# stlink.net
KiCad netlist of a schematic drawn in Altium Designer
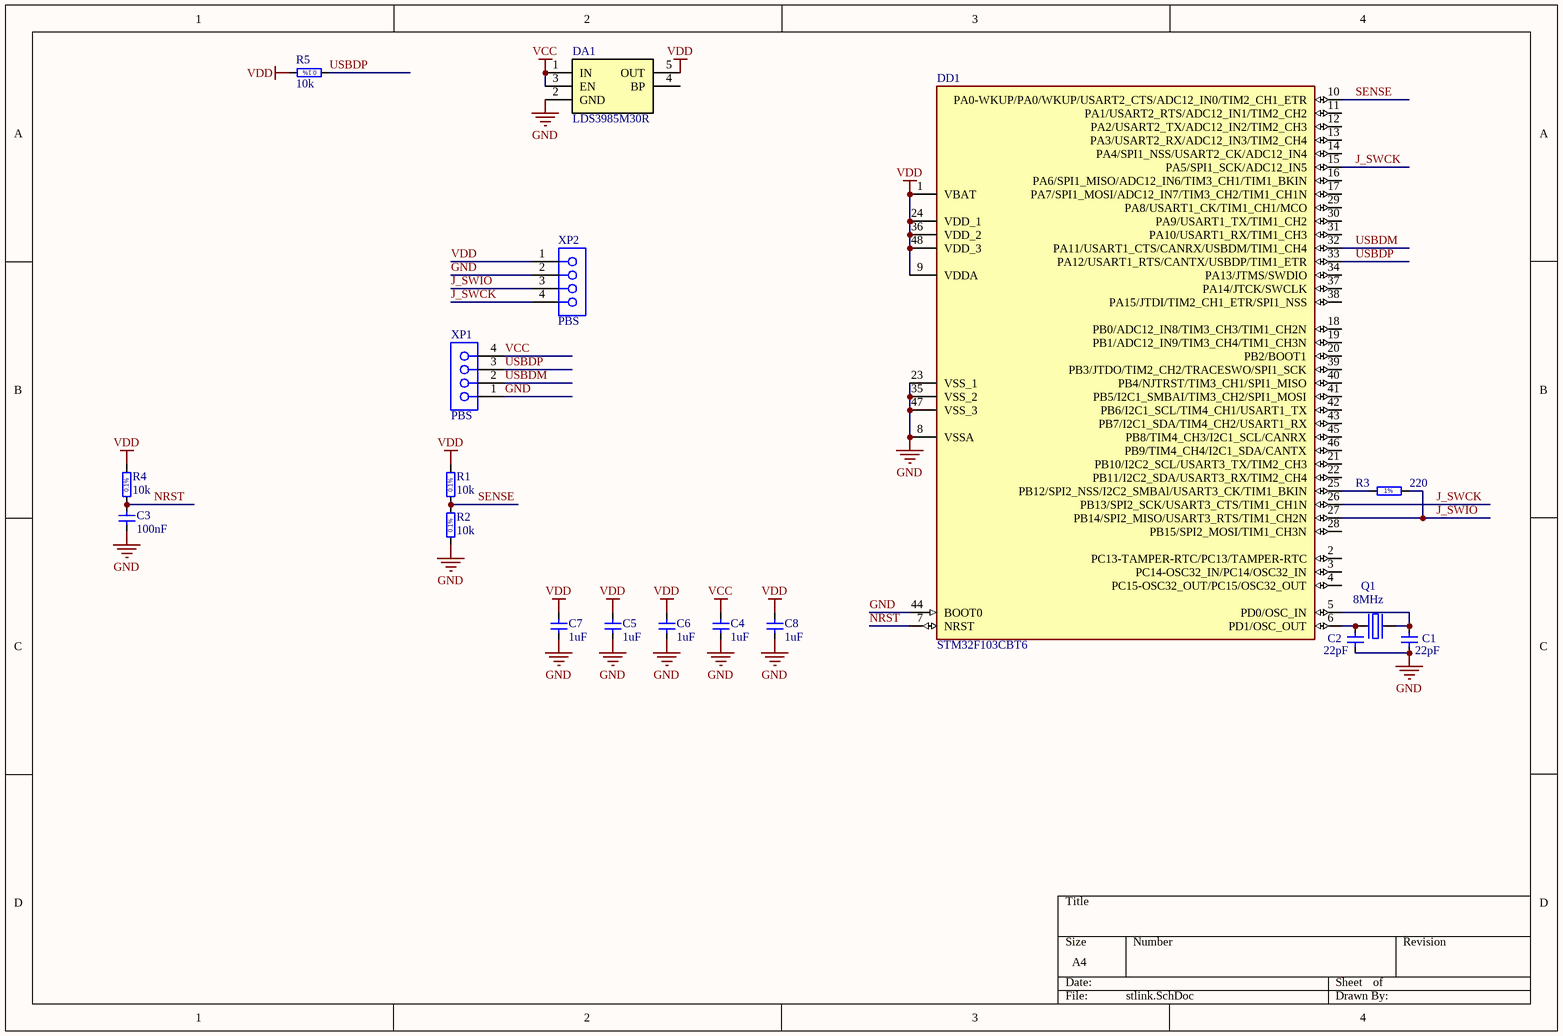
[diagram p0: stlink.SchDoc]

(export (version "E")
  (design (tool "Eeschema 10.0.6"))
  (components
    (comp (ref "C1")
      (value "22pF")
      (footprint "CAP0603R")
      (description "SMD 0805 Capacitor")
      (fields
        (field (name "PART NUMBER") "CC0603_22PF_50V_5%_NP0")
        (field (name "VOLTAGE") "50V")
        (field (name "AUTHOR") "I. Kuznetsov")
      )
      (libsource (lib "Capacitor") (part "CAP_NON_POLAR"))
    )
    (comp (ref "C2")
      (value "22pF")
      (footprint "CAP0603R")
      (description "SMD 0805 Capacitor")
      (fields
        (field (name "PART NUMBER") "CC0603_22PF_50V_5%_NP0")
        (field (name "VOLTAGE") "50V")
        (field (name "AUTHOR") "I. Kuznetsov")
      )
      (libsource (lib "Capacitor") (part "CAP_NON_POLAR"))
    )
    (comp (ref "C3")
      (value "100nF")
      (footprint "CAP0603R")
      (description "SMD 0805 Capacitor")
      (fields
        (field (name "PART NUMBER") "CC0603_100NF_100V_10%_X7R")
        (field (name "VOLTAGE") "100V")
        (field (name "AUTHOR") "I. Kuznetsov")
      )
      (libsource (lib "Capacitor") (part "CAP_NON_POLAR"))
    )
    (comp (ref "C4")
      (value "1uF")
      (footprint "CAP0603R")
      (description "SMD 0805 Capacitor")
      (fields
        (field (name "PART NUMBER") "CC0603_1UF_25V_10%_X7R")
        (field (name "VOLTAGE") "25V")
        (field (name "AUTHOR") "I. Kuznetsov")
      )
      (libsource (lib "Capacitor") (part "CAP_NON_POLAR"))
    )
    (comp (ref "C5")
      (value "1uF")
      (footprint "CAP0603R")
      (description "SMD 0805 Capacitor")
      (fields
        (field (name "PART NUMBER") "CC0603_1UF_25V_10%_X7R")
        (field (name "VOLTAGE") "25V")
        (field (name "AUTHOR") "I. Kuznetsov")
      )
      (libsource (lib "Capacitor") (part "CAP_NON_POLAR"))
    )
    (comp (ref "C6")
      (value "1uF")
      (footprint "CAP0603R")
      (description "SMD 0805 Capacitor")
      (fields
        (field (name "PART NUMBER") "CC0603_1UF_25V_10%_X7R")
        (field (name "VOLTAGE") "25V")
        (field (name "AUTHOR") "I. Kuznetsov")
      )
      (libsource (lib "Capacitor") (part "CAP_NON_POLAR"))
    )
    (comp (ref "C7")
      (value "1uF")
      (footprint "CAP0603R")
      (description "SMD 0805 Capacitor")
      (fields
        (field (name "PART NUMBER") "CC0603_1UF_25V_10%_X7R")
        (field (name "VOLTAGE") "25V")
        (field (name "AUTHOR") "I. Kuznetsov")
      )
      (libsource (lib "Capacitor") (part "CAP_NON_POLAR"))
    )
    (comp (ref "C8")
      (value "1uF")
      (footprint "CAP0603R")
      (description "SMD 0805 Capacitor")
      (fields
        (field (name "PART NUMBER") "CC0603_1UF_25V_10%_X7R")
        (field (name "VOLTAGE") "25V")
        (field (name "AUTHOR") "I. Kuznetsov")
      )
      (libsource (lib "Capacitor") (part "CAP_NON_POLAR"))
    )
    (comp (ref "DA1")
      (value "LDS3985M30R")
      (footprint "SOT23-5")
      (fields (field (name "MANUFACTURER") "ST") (field (name "AUTHOR") "I. Kuznetsov"))
      (libsource (lib "IC And Semiconductor") (part "REG_5_PIN"))
    )
    (comp (ref "DD1")
      (value "STM32F103CBT6")
      (footprint "LQFP48")
      (libsource (lib "IC And Semiconductor") (part "STM32F103X8_B-SQ48"))
    )
    (comp (ref "Q1")
      (value "8MHz")
      (footprint "XTAL_HC-49/U")
      (description "Quartz Crystal")
      (fields
        (field (name "PART NUMBER") "XTAL_20MHZ_AEL_HC-49/U")
        (field (name "MANUFACTURER") "AEL CRYSTALS")
        (field (name "AUTHOR") "CERN DEM JMW")
      )
      (libsource (lib "ICs And Semiconductors") (part "Quartz Crystal"))
    )
    (comp (ref "R1")
      (value "10k")
      (footprint "RES0603R")
      (fields
        (field (name "PART NUMBER") "R0603_10K_0.1%_0.063W_10PPM")
        (field (name "POWER") "0.063W")
        (field (name "TOLERANCE") "±0.1%")
        (field (name "AUTHOR") "CERN DEM JLC")
      )
      (libsource (lib "Resistor") (part "Resistor - 0.1%"))
    )
    (comp (ref "R2")
      (value "10k")
      (footprint "RES0603R")
      (fields
        (field (name "PART NUMBER") "R0603_10K_0.1%_0.063W_10PPM")
        (field (name "POWER") "0.063W")
        (field (name "TOLERANCE") "±0.1%")
        (field (name "AUTHOR") "CERN DEM JLC")
      )
      (libsource (lib "Resistor") (part "Resistor - 0.1%"))
    )
    (comp (ref "R3")
      (value "220")
      (footprint "RES0603R")
      (fields
        (field (name "PART NUMBER") "R0603_220R_1%_0.1W_100PPM")
        (field (name "POWER") "0.1W")
        (field (name "TOLERANCE") "±1%")
        (field (name "AUTHOR") "CERN DEM JLC")
      )
      (libsource (lib "Resistor") (part "Resistor - 1%"))
    )
    (comp (ref "R4")
      (value "10k")
      (footprint "RES0603R")
      (fields
        (field (name "PART NUMBER") "R0603_10K_0.1%_0.063W_10PPM")
        (field (name "POWER") "0.063W")
        (field (name "TOLERANCE") "±0.1%")
        (field (name "AUTHOR") "CERN DEM JLC")
      )
      (libsource (lib "Resistor") (part "Resistor - 0.1%"))
    )
    (comp (ref "R5")
      (value "10k")
      (footprint "RES0603R")
      (fields
        (field (name "PART NUMBER") "R0603_10K_0.1%_0.063W_10PPM")
        (field (name "POWER") "0.063W")
        (field (name "TOLERANCE") "±0.1%")
        (field (name "AUTHOR") "CERN DEM JLC")
      )
      (libsource (lib "Resistor") (part "Resistor - 0.1%"))
    )
    (comp (ref "XP1")
      (value "PBS")
      (footprint "PBS-04")
      (fields (field (name "PART NUMBER") "PBS-04"))
      (libsource (lib "") (part "CN_04S_1W_1"))
    )
    (comp (ref "XP2")
      (value "PBS")
      (footprint "PBS-04")
      (fields (field (name "PART NUMBER") "PBS-04"))
      (libsource (lib "Connector") (part "CN_04S_1W"))
    )
  )
  (nets
    (net (code "1") (name "/J_SWCK") (class "Default")
      (node (ref "DD1") (pin "15") (pinfunction "PA5/SPI1_SCK/ADC12_IN5_15") (pintype "bidirectional"))
      (node (ref "DD1") (pin "26") (pinfunction "PB13/SPI2_SCK/USART3_CTS/TIM1_CH1N_26") (pintype "bidirectional"))
      (node (ref "XP2") (pin "4") (pinfunction "4_4") (pintype "passive"))
    )
    (net (code "2") (name "/J_SWIO") (class "Default")
      (node (ref "DD1") (pin "27") (pinfunction "PB14/SPI2_MISO/USART3_RTS/TIM1_CH2N_27") (pintype "bidirectional"))
      (node (ref "R3") (pin "2") (pinfunction "2_2") (pintype "passive"))
      (node (ref "XP2") (pin "3") (pinfunction "3_3") (pintype "passive"))
    )
    (net (code "3") (name "/NRST") (class "Default")
      (node (ref "C3") (pin "2") (pinfunction "2_2") (pintype "passive"))
      (node (ref "DD1") (pin "7") (pinfunction "NRST_7") (pintype "bidirectional"))
      (node (ref "R4") (pin "1") (pinfunction "1_1") (pintype "passive"))
    )
    (net (code "4") (name "/SENSE") (class "Default")
      (node (ref "DD1") (pin "10") (pinfunction "PA0-WKUP/PA0/WKUP/USART2_CTS/ADC12_IN0/TIM2_CH1_ETR_10") (pintype "bidirectional"))
      (node (ref "R1") (pin "1") (pinfunction "1_1") (pintype "passive"))
      (node (ref "R2") (pin "2") (pinfunction "2_2") (pintype "passive"))
    )
    (net (code "5") (name "/USBDM") (class "Default")
      (node (ref "DD1") (pin "32") (pinfunction "PA11/USART1_CTS/CANRX/USBDM/TIM1_CH4_32") (pintype "bidirectional"))
      (node (ref "XP1") (pin "2") (pinfunction "2_2") (pintype "passive"))
    )
    (net (code "6") (name "/USBDP") (class "Default")
      (node (ref "DD1") (pin "33") (pinfunction "PA12/USART1_RTS/CANTX/USBDP/TIM1_ETR_33") (pintype "bidirectional"))
      (node (ref "R5") (pin "1") (pinfunction "1_1") (pintype "passive"))
      (node (ref "XP1") (pin "3") (pinfunction "3_3") (pintype "passive"))
    )
    (net (code "7") (name "GND") (class "Default")
      (node (ref "C1") (pin "1") (pinfunction "1_1") (pintype "passive"))
      (node (ref "C2") (pin "1") (pinfunction "1_1") (pintype "passive"))
      (node (ref "C3") (pin "1") (pinfunction "1_1") (pintype "passive"))
      (node (ref "C4") (pin "1") (pinfunction "1_1") (pintype "passive"))
      (node (ref "C5") (pin "1") (pinfunction "1_1") (pintype "passive"))
      (node (ref "C6") (pin "1") (pinfunction "1_1") (pintype "passive"))
      (node (ref "C7") (pin "1") (pinfunction "1_1") (pintype "passive"))
      (node (ref "C8") (pin "1") (pinfunction "1_1") (pintype "passive"))
      (node (ref "DA1") (pin "2") (pinfunction "GND_2") (pintype "passive"))
      (node (ref "DD1") (pin "23") (pinfunction "VSS_1_23") (pintype "power_in"))
      (node (ref "DD1") (pin "35") (pinfunction "VSS_2_35") (pintype "power_in"))
      (node (ref "DD1") (pin "44") (pinfunction "BOOT0_44") (pintype "input"))
      (node (ref "DD1") (pin "47") (pinfunction "VSS_3_47") (pintype "power_in"))
      (node (ref "DD1") (pin "8") (pinfunction "VSSA_8") (pintype "power_in"))
      (node (ref "R2") (pin "1") (pinfunction "1_1") (pintype "passive"))
      (node (ref "XP1") (pin "1") (pinfunction "1_1") (pintype "passive"))
      (node (ref "XP2") (pin "2") (pinfunction "2_2") (pintype "passive"))
    )
    (net (code "8") (name "Net-(DD1-PB12{slash}SPI2_NSS{slash}I2C2_SMBAl{slash}USART3_CK{slash}TIM1_BKIN)") (class "Default")
      (node (ref "DD1") (pin "25") (pinfunction "PB12/SPI2_NSS/I2C2_SMBAl/USART3_CK/TIM1_BKIN_25") (pintype "bidirectional"))
      (node (ref "R3") (pin "1") (pinfunction "1_1") (pintype "passive"))
    )
    (net (code "9") (name "Net-(DD1-PD0{slash}OSC_IN)") (class "Default")
      (node (ref "C1") (pin "2") (pinfunction "2_2") (pintype "passive"))
      (node (ref "DD1") (pin "5") (pinfunction "PD0/OSC_IN_5") (pintype "bidirectional"))
      (node (ref "Q1") (pin "2") (pinfunction "OSC2_2") (pintype "passive"))
    )
    (net (code "10") (name "Net-(DD1-PD1{slash}OSC_OUT)") (class "Default")
      (node (ref "C2") (pin "2") (pinfunction "2_2") (pintype "passive"))
      (node (ref "DD1") (pin "6") (pinfunction "PD1/OSC_OUT_6") (pintype "bidirectional"))
      (node (ref "Q1") (pin "1") (pinfunction "OSC1_1") (pintype "passive"))
    )
    (net (code "11") (name "VCC") (class "Default")
      (node (ref "C4") (pin "2") (pinfunction "2_2") (pintype "passive"))
      (node (ref "DA1") (pin "1") (pinfunction "IN_1") (pintype "passive"))
      (node (ref "DA1") (pin "3") (pinfunction "EN_3") (pintype "passive"))
      (node (ref "XP1") (pin "4") (pinfunction "4_4") (pintype "passive"))
    )
    (net (code "12") (name "VDD") (class "Default")
      (node (ref "C5") (pin "2") (pinfunction "2_2") (pintype "passive"))
      (node (ref "C6") (pin "2") (pinfunction "2_2") (pintype "passive"))
      (node (ref "C7") (pin "2") (pinfunction "2_2") (pintype "passive"))
      (node (ref "C8") (pin "2") (pinfunction "2_2") (pintype "passive"))
      (node (ref "DA1") (pin "5") (pinfunction "OUT_5") (pintype "passive"))
      (node (ref "DD1") (pin "1") (pinfunction "VBAT_1") (pintype "power_in"))
      (node (ref "DD1") (pin "24") (pinfunction "VDD_1_24") (pintype "power_in"))
      (node (ref "DD1") (pin "36") (pinfunction "VDD_2_36") (pintype "power_in"))
      (node (ref "DD1") (pin "48") (pinfunction "VDD_3_48") (pintype "power_in"))
      (node (ref "DD1") (pin "9") (pinfunction "VDDA_9") (pintype "power_in"))
      (node (ref "R1") (pin "2") (pinfunction "2_2") (pintype "passive"))
      (node (ref "R4") (pin "2") (pinfunction "2_2") (pintype "passive"))
      (node (ref "R5") (pin "2") (pinfunction "2_2") (pintype "passive"))
      (node (ref "XP2") (pin "1") (pinfunction "1_1") (pintype "passive"))
    )
    (net (code "13") (name "unconnected-(DA1-BP-Pad4)") (class "Default")
      (node (ref "DA1") (pin "4") (pinfunction "BP_4") (pintype "passive"))
    )
    (net (code "14") (name "unconnected-(DD1-PA1{slash}USART2_RTS{slash}ADC12_IN1{slash}TIM2_CH2-Pad11)") (class "Default")
      (node (ref "DD1") (pin "11") (pinfunction "PA1/USART2_RTS/ADC12_IN1/TIM2_CH2_11") (pintype "bidirectional"))
    )
    (net (code "15") (name "unconnected-(DD1-PA2{slash}USART2_TX{slash}ADC12_IN2{slash}TIM2_CH3-Pad12)") (class "Default")
      (node (ref "DD1") (pin "12") (pinfunction "PA2/USART2_TX/ADC12_IN2/TIM2_CH3_12") (pintype "bidirectional"))
    )
    (net (code "16") (name "unconnected-(DD1-PA3{slash}USART2_RX{slash}ADC12_IN3{slash}TIM2_CH4-Pad13)") (class "Default")
      (node (ref "DD1") (pin "13") (pinfunction "PA3/USART2_RX/ADC12_IN3/TIM2_CH4_13") (pintype "bidirectional"))
    )
    (net (code "17") (name "unconnected-(DD1-PA4{slash}SPI1_NSS{slash}USART2_CK{slash}ADC12_IN4-Pad14)") (class "Default")
      (node (ref "DD1") (pin "14") (pinfunction "PA4/SPI1_NSS/USART2_CK/ADC12_IN4_14") (pintype "bidirectional"))
    )
    (net (code "18") (name "unconnected-(DD1-PA6{slash}SPI1_MISO{slash}ADC12_IN6{slash}TIM3_CH1{slash}TIM1_BKIN-Pad16)") (class "Default")
      (node (ref "DD1") (pin "16") (pinfunction "PA6/SPI1_MISO/ADC12_IN6/TIM3_CH1/TIM1_BKIN_16") (pintype "bidirectional"))
    )
    (net (code "19") (name "unconnected-(DD1-PA7{slash}SPI1_MOSI{slash}ADC12_IN7{slash}TIM3_CH2{slash}TIM1_CH1N-Pad17)") (class "Default")
      (node (ref "DD1") (pin "17") (pinfunction "PA7/SPI1_MOSI/ADC12_IN7/TIM3_CH2/TIM1_CH1N_17") (pintype "bidirectional"))
    )
    (net (code "20") (name "unconnected-(DD1-PA8{slash}USART1_CK{slash}TIM1_CH1{slash}MCO-Pad29)") (class "Default")
      (node (ref "DD1") (pin "29") (pinfunction "PA8/USART1_CK/TIM1_CH1/MCO_29") (pintype "bidirectional"))
    )
    (net (code "21") (name "unconnected-(DD1-PA9{slash}USART1_TX{slash}TIM1_CH2-Pad30)") (class "Default")
      (node (ref "DD1") (pin "30") (pinfunction "PA9/USART1_TX/TIM1_CH2_30") (pintype "bidirectional"))
    )
    (net (code "22") (name "unconnected-(DD1-PA10{slash}USART1_RX{slash}TIM1_CH3-Pad31)") (class "Default")
      (node (ref "DD1") (pin "31") (pinfunction "PA10/USART1_RX/TIM1_CH3_31") (pintype "bidirectional"))
    )
    (net (code "23") (name "unconnected-(DD1-PA13{slash}JTMS{slash}SWDIO-Pad34)") (class "Default")
      (node (ref "DD1") (pin "34") (pinfunction "PA13/JTMS/SWDIO_34") (pintype "bidirectional"))
    )
    (net (code "24") (name "unconnected-(DD1-PA14{slash}JTCK{slash}SWCLK-Pad37)") (class "Default")
      (node (ref "DD1") (pin "37") (pinfunction "PA14/JTCK/SWCLK_37") (pintype "bidirectional"))
    )
    (net (code "25") (name "unconnected-(DD1-PA15{slash}JTDI{slash}TIM2_CH1_ETR{slash}SPI1_NSS-Pad38)") (class "Default")
      (node (ref "DD1") (pin "38") (pinfunction "PA15/JTDI/TIM2_CH1_ETR/SPI1_NSS_38") (pintype "bidirectional"))
    )
    (net (code "26") (name "unconnected-(DD1-PB0{slash}ADC12_IN8{slash}TIM3_CH3{slash}TIM1_CH2N-Pad18)") (class "Default")
      (node (ref "DD1") (pin "18") (pinfunction "PB0/ADC12_IN8/TIM3_CH3/TIM1_CH2N_18") (pintype "bidirectional"))
    )
    (net (code "27") (name "unconnected-(DD1-PB1{slash}ADC12_IN9{slash}TIM3_CH4{slash}TIM1_CH3N-Pad19)") (class "Default")
      (node (ref "DD1") (pin "19") (pinfunction "PB1/ADC12_IN9/TIM3_CH4/TIM1_CH3N_19") (pintype "bidirectional"))
    )
    (net (code "28") (name "unconnected-(DD1-PB2{slash}BOOT1-Pad20)") (class "Default")
      (node (ref "DD1") (pin "20") (pinfunction "PB2/BOOT1_20") (pintype "bidirectional"))
    )
    (net (code "29") (name "unconnected-(DD1-PB3{slash}JTDO{slash}TIM2_CH2{slash}TRACESWO{slash}SPI1_SCK-Pad39)") (class "Default")
      (node (ref "DD1") (pin "39") (pinfunction "PB3/JTDO/TIM2_CH2/TRACESWO/SPI1_SCK_39") (pintype "bidirectional"))
    )
    (net (code "30") (name "unconnected-(DD1-PB4{slash}NJTRST{slash}TIM3_CH1{slash}SPI1_MISO-Pad40)") (class "Default")
      (node (ref "DD1") (pin "40") (pinfunction "PB4/NJTRST/TIM3_CH1/SPI1_MISO_40") (pintype "bidirectional"))
    )
    (net (code "31") (name "unconnected-(DD1-PB5{slash}I2C1_SMBAI{slash}TIM3_CH2{slash}SPI1_MOSI-Pad41)") (class "Default")
      (node (ref "DD1") (pin "41") (pinfunction "PB5/I2C1_SMBAI/TIM3_CH2/SPI1_MOSI_41") (pintype "bidirectional"))
    )
    (net (code "32") (name "unconnected-(DD1-PB6{slash}I2C1_SCL{slash}TIM4_CH1{slash}USART1_TX-Pad42)") (class "Default")
      (node (ref "DD1") (pin "42") (pinfunction "PB6/I2C1_SCL/TIM4_CH1/USART1_TX_42") (pintype "bidirectional"))
    )
    (net (code "33") (name "unconnected-(DD1-PB7{slash}I2C1_SDA{slash}TIM4_CH2{slash}USART1_RX-Pad43)") (class "Default")
      (node (ref "DD1") (pin "43") (pinfunction "PB7/I2C1_SDA/TIM4_CH2/USART1_RX_43") (pintype "bidirectional"))
    )
    (net (code "34") (name "unconnected-(DD1-PB8{slash}TIM4_CH3{slash}I2C1_SCL{slash}CANRX-Pad45)") (class "Default")
      (node (ref "DD1") (pin "45") (pinfunction "PB8/TIM4_CH3/I2C1_SCL/CANRX_45") (pintype "bidirectional"))
    )
    (net (code "35") (name "unconnected-(DD1-PB9{slash}TIM4_CH4{slash}I2C1_SDA{slash}CANTX-Pad46)") (class "Default")
      (node (ref "DD1") (pin "46") (pinfunction "PB9/TIM4_CH4/I2C1_SDA/CANTX_46") (pintype "bidirectional"))
    )
    (net (code "36") (name "unconnected-(DD1-PB10{slash}I2C2_SCL{slash}USART3_TX{slash}TIM2_CH3-Pad21)") (class "Default")
      (node (ref "DD1") (pin "21") (pinfunction "PB10/I2C2_SCL/USART3_TX/TIM2_CH3_21") (pintype "bidirectional"))
    )
    (net (code "37") (name "unconnected-(DD1-PB11{slash}I2C2_SDA{slash}USART3_RX{slash}TIM2_CH4-Pad22)") (class "Default")
      (node (ref "DD1") (pin "22") (pinfunction "PB11/I2C2_SDA/USART3_RX/TIM2_CH4_22") (pintype "bidirectional"))
    )
    (net (code "38") (name "unconnected-(DD1-PB15{slash}SPI2_MOSI{slash}TIM1_CH3N-Pad28)") (class "Default")
      (node (ref "DD1") (pin "28") (pinfunction "PB15/SPI2_MOSI/TIM1_CH3N_28") (pintype "bidirectional"))
    )
    (net (code "39") (name "unconnected-(DD1-PC13-TAMPER-RTC{slash}PC13{slash}TAMPER-RTC-Pad2)") (class "Default")
      (node (ref "DD1") (pin "2") (pinfunction "PC13-TAMPER-RTC/PC13/TAMPER-RTC_2") (pintype "bidirectional"))
    )
    (net (code "40") (name "unconnected-(DD1-PC14-OSC32_IN{slash}PC14{slash}OSC32_IN-Pad3)") (class "Default")
      (node (ref "DD1") (pin "3") (pinfunction "PC14-OSC32_IN/PC14/OSC32_IN_3") (pintype "bidirectional"))
    )
    (net (code "41") (name "unconnected-(DD1-PC15-OSC32_OUT{slash}PC15{slash}OSC32_OUT-Pad4)") (class "Default")
      (node (ref "DD1") (pin "4") (pinfunction "PC15-OSC32_OUT/PC15/OSC32_OUT_4") (pintype "bidirectional"))
    )
  )
)
